# minimatrix.net
KiCad netlist of a schematic drawn in EAGLE
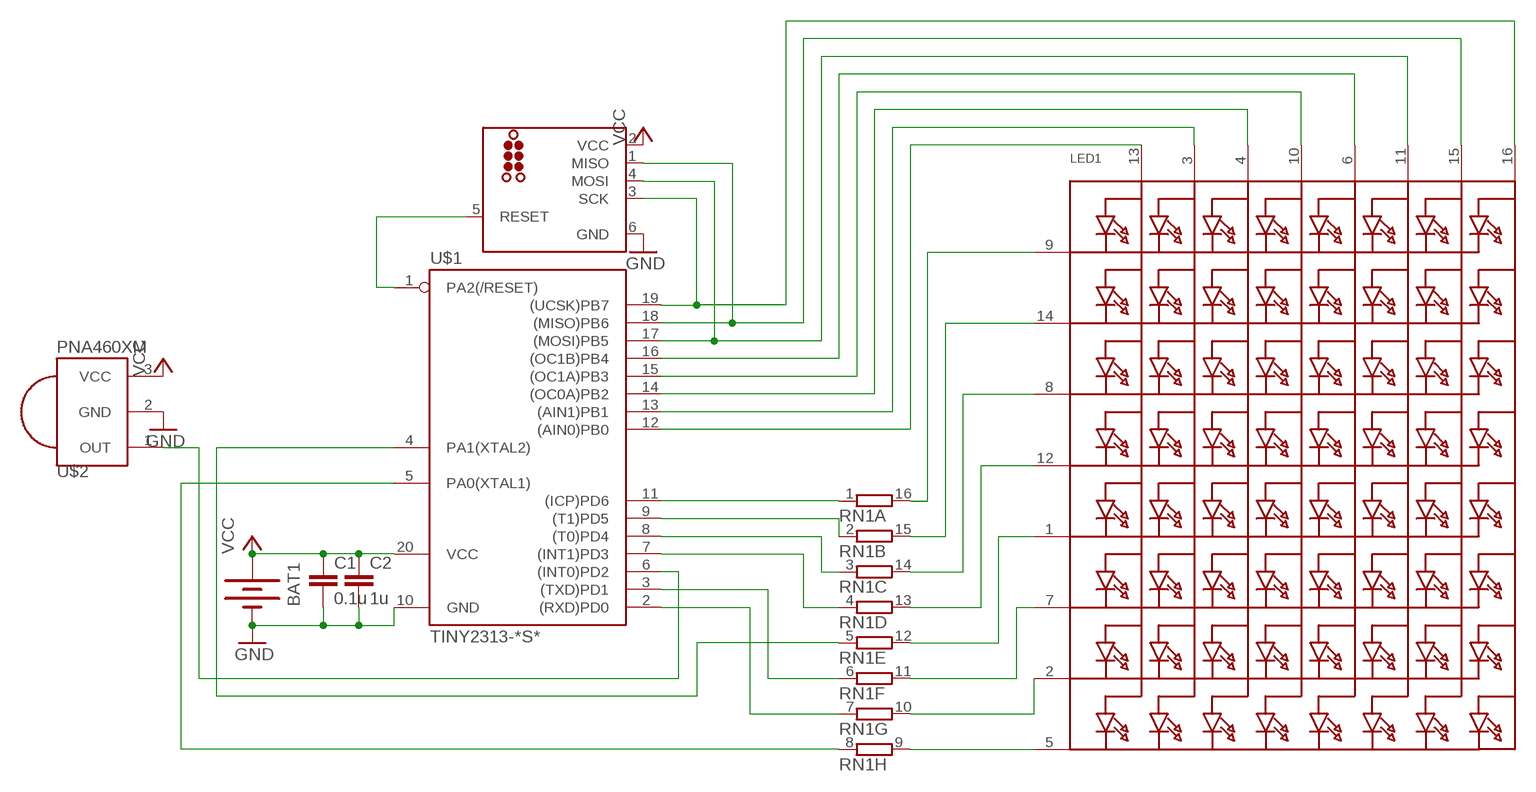
[diagram p0: schematic, sheet 1]

(export (version "E")
  (design (tool "Eeschema 10.0.6"))
  (components
    (comp (ref "BAT1")
      (value "BATTERY20MM_4LEGS")
      (footprint "eagle-import:BATTCON_20MM_4LEGS")
      (libsource (lib "eagle-import") (part "BATTERY20MM_4LEGS"))
    )
    (comp (ref "C1")
      (value "0.1u")
      (footprint "eagle-import:0805")
      (libsource (lib "eagle-import") (part "CAP0805"))
    )
    (comp (ref "C2")
      (value "1u")
      (footprint "eagle-import:0805")
      (libsource (lib "eagle-import") (part "CAP0805"))
    )
    (comp (ref "LED1")
      (value "SEGMENT_8X8_ROWCATHODEM12A881UR")
      (footprint "eagle-import:SEGMENT_BL-M12A881UR")
      (libsource (lib "eagle-import") (part "SEGMENT_8X8_ROWCATHODEM12A881UR"))
    )
    (comp (ref "RN1")
      (value "8R-NEXB2HV")
      (footprint "eagle-import:EXB2HV")
      (libsource (lib "eagle-import") (part "8R-NEXB2HV"))
    )
    (comp (ref "U$1")
      (value "TINY2313-*S*")
      (footprint "eagle-import:SO20L$")
      (libsource (lib "eagle-import") (part "TINY2313-S"))
    )
    (comp (ref "U$2")
      (value "PNA460XM")
      (footprint "eagle-import:PNA460XM")
      (libsource (lib "eagle-import") (part "PNA460XM"))
    )
    (comp (ref "U$3")
      (value "TC2030_AVRMCP-NL")
      (footprint "eagle-import:TC2030-MCP-NL")
      (libsource (lib "eagle-import") (part "TC2030_AVRMCP-NL"))
    )
  )
  (nets
    (net (code "1") (name "GND") (class "Default")
      (node (ref "BAT1") (pin "2") (pinfunction "-_2") (pintype "power_in"))
      (node (ref "C1") (pin "2") (pinfunction "2_2") (pintype "passive"))
      (node (ref "C2") (pin "2") (pinfunction "2_2") (pintype "passive"))
      (node (ref "U$1") (pin "10") (pinfunction "GND_10") (pintype "power_in"))
      (node (ref "U$2") (pin "2") (pinfunction "GND_2") (pintype "power_in"))
      (node (ref "U$3") (pin "6") (pinfunction "GND_6") (pintype "power_in"))
    )
    (net (code "2") (name "Net-(LED1-A1)") (class "Default")
      (node (ref "LED1") (pin "13") (pinfunction "A1_13") (pintype "bidirectional"))
      (node (ref "U$1") (pin "12") (pinfunction "(AIN0)PB0_12") (pintype "bidirectional"))
    )
    (net (code "3") (name "Net-(LED1-A2)") (class "Default")
      (node (ref "LED1") (pin "3") (pinfunction "A2_3") (pintype "bidirectional"))
      (node (ref "U$1") (pin "13") (pinfunction "(AIN1)PB1_13") (pintype "bidirectional"))
    )
    (net (code "4") (name "Net-(LED1-A3)") (class "Default")
      (node (ref "LED1") (pin "4") (pinfunction "A3_4") (pintype "bidirectional"))
      (node (ref "U$1") (pin "14") (pinfunction "(OC0A)PB2_14") (pintype "bidirectional"))
    )
    (net (code "5") (name "Net-(LED1-A4)") (class "Default")
      (node (ref "LED1") (pin "10") (pinfunction "A4_10") (pintype "bidirectional"))
      (node (ref "U$1") (pin "15") (pinfunction "(OC1A)PB3_15") (pintype "bidirectional"))
    )
    (net (code "6") (name "Net-(LED1-A5)") (class "Default")
      (node (ref "LED1") (pin "6") (pinfunction "A5_6") (pintype "bidirectional"))
      (node (ref "U$1") (pin "16") (pinfunction "(OC1B)PB4_16") (pintype "bidirectional"))
    )
    (net (code "7") (name "Net-(LED1-A6)") (class "Default")
      (node (ref "LED1") (pin "11") (pinfunction "A6_11") (pintype "bidirectional"))
      (node (ref "U$1") (pin "17") (pinfunction "(MOSI)PB5_17") (pintype "bidirectional"))
      (node (ref "U$3") (pin "4") (pinfunction "MOSI_4") (pintype "input"))
    )
    (net (code "8") (name "Net-(LED1-A7)") (class "Default")
      (node (ref "LED1") (pin "15") (pinfunction "A7_15") (pintype "bidirectional"))
      (node (ref "U$1") (pin "18") (pinfunction "(MISO)PB6_18") (pintype "bidirectional"))
      (node (ref "U$3") (pin "1") (pinfunction "MISO_1") (pintype "output"))
    )
    (net (code "9") (name "Net-(LED1-A8)") (class "Default")
      (node (ref "LED1") (pin "16") (pinfunction "A8_16") (pintype "bidirectional"))
      (node (ref "U$1") (pin "19") (pinfunction "(UCSK)PB7_19") (pintype "bidirectional"))
      (node (ref "U$3") (pin "3") (pinfunction "SCK_3") (pintype "output"))
    )
    (net (code "10") (name "Net-(LED1-K1)") (class "Default")
      (node (ref "LED1") (pin "9") (pinfunction "K1_9") (pintype "bidirectional"))
      (node (ref "RN1") (pin "16") (pinfunction "2_16") (pintype "passive"))
    )
    (net (code "11") (name "Net-(LED1-K2)") (class "Default")
      (node (ref "LED1") (pin "14") (pinfunction "K2_14") (pintype "bidirectional"))
      (node (ref "RN1") (pin "15") (pinfunction "2_15") (pintype "passive"))
    )
    (net (code "12") (name "Net-(LED1-K3)") (class "Default")
      (node (ref "LED1") (pin "8") (pinfunction "K3_8") (pintype "bidirectional"))
      (node (ref "RN1") (pin "14") (pinfunction "2_14") (pintype "passive"))
    )
    (net (code "13") (name "Net-(LED1-K4)") (class "Default")
      (node (ref "LED1") (pin "12") (pinfunction "K4_12") (pintype "bidirectional"))
      (node (ref "RN1") (pin "13") (pinfunction "2_13") (pintype "passive"))
    )
    (net (code "14") (name "Net-(LED1-K5)") (class "Default")
      (node (ref "LED1") (pin "1") (pinfunction "K5_1") (pintype "bidirectional"))
      (node (ref "RN1") (pin "12") (pinfunction "2_12") (pintype "passive"))
    )
    (net (code "15") (name "Net-(LED1-K6)") (class "Default")
      (node (ref "LED1") (pin "7") (pinfunction "K6_7") (pintype "bidirectional"))
      (node (ref "RN1") (pin "11") (pinfunction "2_11") (pintype "passive"))
    )
    (net (code "16") (name "Net-(LED1-K7)") (class "Default")
      (node (ref "LED1") (pin "2") (pinfunction "K7_2") (pintype "bidirectional"))
      (node (ref "RN1") (pin "10") (pinfunction "2_10") (pintype "passive"))
    )
    (net (code "17") (name "Net-(LED1-K8)") (class "Default")
      (node (ref "LED1") (pin "5") (pinfunction "K8_5") (pintype "bidirectional"))
      (node (ref "RN1") (pin "9") (pinfunction "2_9") (pintype "passive"))
    )
    (net (code "18") (name "Net-(RN1B-1)") (class "Default")
      (node (ref "RN1") (pin "2") (pinfunction "1_2") (pintype "passive"))
      (node (ref "U$1") (pin "9") (pinfunction "(T1)PD5_9") (pintype "bidirectional"))
    )
    (net (code "19") (name "Net-(RN1C-1)") (class "Default")
      (node (ref "RN1") (pin "3") (pinfunction "1_3") (pintype "passive"))
      (node (ref "U$1") (pin "8") (pinfunction "(T0)PD4_8") (pintype "bidirectional"))
    )
    (net (code "20") (name "Net-(RN1D-1)") (class "Default")
      (node (ref "RN1") (pin "4") (pinfunction "1_4") (pintype "passive"))
      (node (ref "U$1") (pin "7") (pinfunction "(INT1)PD3_7") (pintype "bidirectional"))
    )
    (net (code "21") (name "Net-(RN1E-1)") (class "Default")
      (node (ref "RN1") (pin "5") (pinfunction "1_5") (pintype "passive"))
      (node (ref "U$1") (pin "4") (pinfunction "PA1(XTAL2)_4") (pintype "bidirectional"))
    )
    (net (code "22") (name "Net-(RN1F-1)") (class "Default")
      (node (ref "RN1") (pin "6") (pinfunction "1_6") (pintype "passive"))
      (node (ref "U$1") (pin "3") (pinfunction "(TXD)PD1_3") (pintype "bidirectional"))
    )
    (net (code "23") (name "Net-(RN1G-1)") (class "Default")
      (node (ref "RN1") (pin "7") (pinfunction "1_7") (pintype "passive"))
      (node (ref "U$1") (pin "2") (pinfunction "(RXD)PD0_2") (pintype "bidirectional"))
    )
    (net (code "24") (name "Net-(RN1H-1)") (class "Default")
      (node (ref "RN1") (pin "8") (pinfunction "1_8") (pintype "passive"))
      (node (ref "U$1") (pin "5") (pinfunction "PA0(XTAL1)_5") (pintype "bidirectional"))
    )
    (net (code "25") (name "Net-(U$1-(ICP)PD6)") (class "Default")
      (node (ref "RN1") (pin "1") (pinfunction "1_1") (pintype "passive"))
      (node (ref "U$1") (pin "11") (pinfunction "(ICP)PD6_11") (pintype "bidirectional"))
    )
    (net (code "26") (name "Net-(U$1-(INT0)PD2)") (class "Default")
      (node (ref "U$1") (pin "6") (pinfunction "(INT0)PD2_6") (pintype "bidirectional"))
      (node (ref "U$2") (pin "1") (pinfunction "OUT_1") (pintype "output"))
    )
    (net (code "27") (name "Net-(U$1-PA2({slash}RESET))") (class "Default")
      (node (ref "U$1") (pin "1") (pinfunction "PA2(/RESET)_1") (pintype "input"))
      (node (ref "U$3") (pin "5") (pinfunction "RESET_5") (pintype "output"))
    )
    (net (code "28") (name "VCC") (class "Default")
      (node (ref "BAT1") (pin "1") (pinfunction "+_1") (pintype "power_in"))
      (node (ref "C1") (pin "1") (pinfunction "1_1") (pintype "passive"))
      (node (ref "C2") (pin "1") (pinfunction "1_1") (pintype "passive"))
      (node (ref "U$1") (pin "20") (pinfunction "VCC_20") (pintype "power_in"))
      (node (ref "U$2") (pin "3") (pinfunction "VCC_3") (pintype "power_in"))
      (node (ref "U$3") (pin "2") (pinfunction "VCC_2") (pintype "power_in"))
    )
  )
)
